# Particle-Gateway.net
KiCad netlist of a schematic drawn in EAGLE
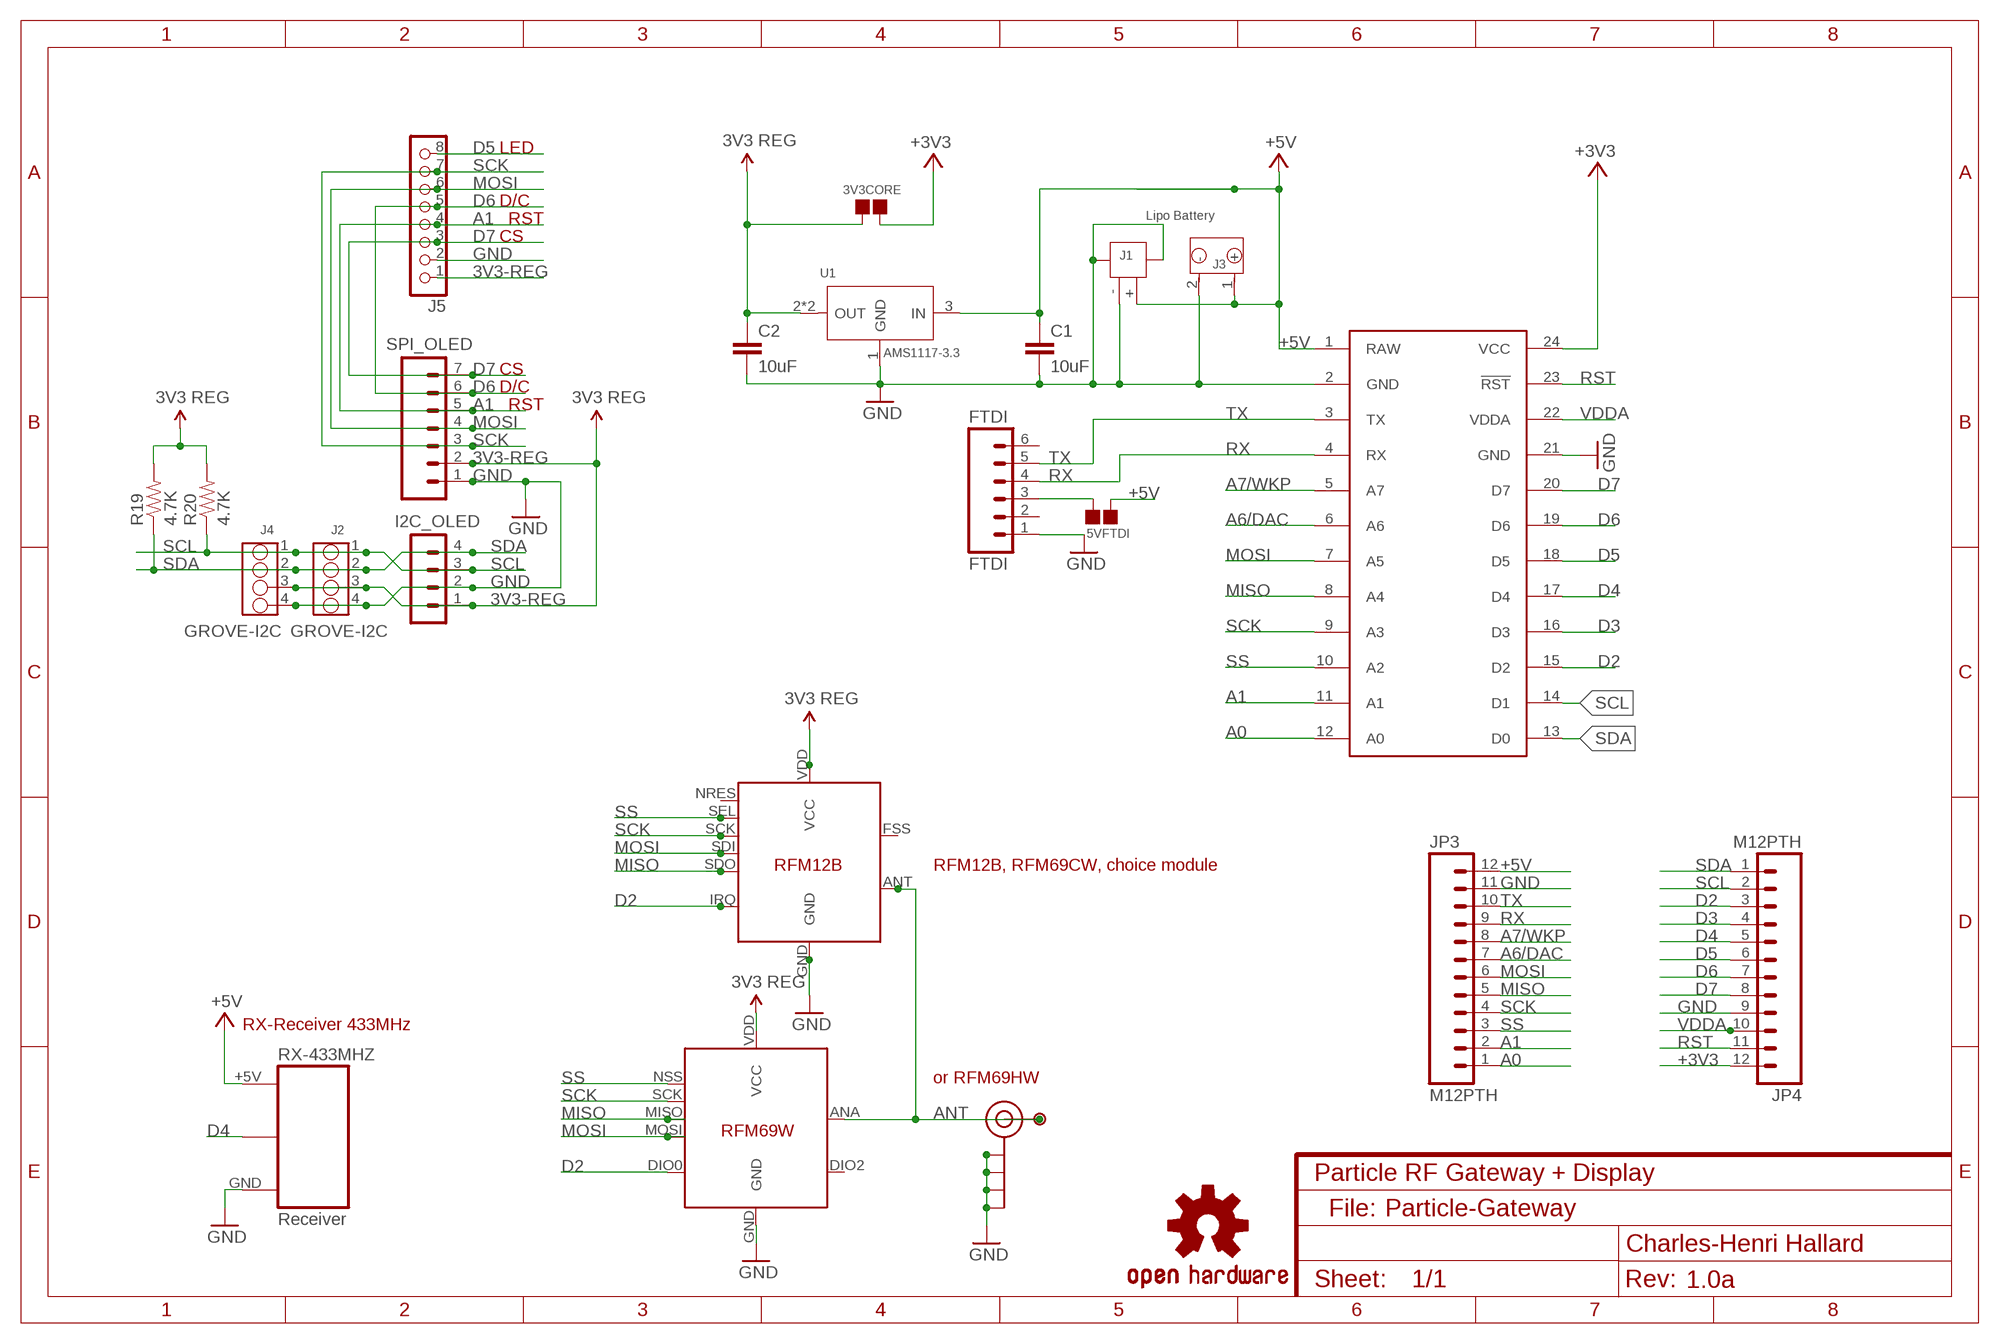
[diagram p0: schematic, sheet 1]

(export (version "E")
  (design (tool "Eeschema 10.0.6"))
  (components
    (comp (ref "3V3CORE")
      (value "PAD-JUMPER-2P")
      (footprint "eagle-import:2P-SMD-1.78X1.27")
      (fields (field (name "PARTNO") "DNP"))
      (libsource (lib "eagle-import") (part "PAD-JUMPER-2P"))
    )
    (comp (ref "5VFTDI")
      (value "PAD-JUMPER-2P")
      (footprint "eagle-import:2P-SMD-1.78X1.27")
      (fields (field (name "PARTNO") "DNP"))
      (libsource (lib "eagle-import") (part "PAD-JUMPER-2P"))
    )
    (comp (ref "C1")
      (value "10uF")
      (footprint "eagle-import:0805-CAP")
      (libsource (lib "eagle-import") (part "CAP0805-CAP"))
    )
    (comp (ref "C2")
      (value "10uF")
      (footprint "eagle-import:0805-CAP")
      (libsource (lib "eagle-import") (part "CAP0805-CAP"))
    )
    (comp (ref "FTDI")
      (value "FTDI")
      (footprint "eagle-import:1X06")
      (libsource (lib "eagle-import") (part "M06SIP"))
    )
    (comp (ref "I2C_OLED")
      (value "CON_HEADER_1X04'SMALL''")
      (footprint "eagle-import:M1X4")
      (libsource (lib "eagle-import") (part "CON_HEADER_1X04'SMALL''"))
    )
    (comp (ref "J$1")
      (value "SMA_EDGE")
      (footprint "eagle-import:SMA-EDGE")
      (libsource (lib "eagle-import") (part "SMA_EDGE"))
    )
    (comp (ref "J1")
      (value "JST-2P-SMD'2.0'")
      (footprint "eagle-import:2P-SMD-2.0-90D")
      (libsource (lib "eagle-import") (part "JST-2P-SMD'2.0'"))
    )
    (comp (ref "J2")
      (value "GROVE-I2C")
      (footprint "eagle-import:4P-2.0-90D")
      (libsource (lib "eagle-import") (part "GROVE-4P-2.0-3470140P1"))
    )
    (comp (ref "J3")
      (value "Lipo Battery")
      (footprint "eagle-import:2P-2.0-90D")
      (libsource (lib "eagle-import") (part "JST-2P-PW-3410070P1"))
    )
    (comp (ref "J4")
      (value "GROVE-I2C")
      (footprint "eagle-import:4P-2.0")
      (libsource (lib "eagle-import") (part "GROVE-4P-2.0-3470130P1"))
    )
    (comp (ref "J5")
      (value "CON_HEADER_1X08-PTH")
      (footprint "eagle-import:M1X8")
      (libsource (lib "eagle-import") (part "CON_HEADER_1X08-PTH"))
    )
    (comp (ref "JP3")
      (value "M12PTH")
      (footprint "eagle-import:1X12-SMALL-PADS")
      (libsource (lib "eagle-import") (part "M12PTH"))
    )
    (comp (ref "JP4")
      (value "M12PTH")
      (footprint "eagle-import:1X12-SMALL-PADS")
      (libsource (lib "eagle-import") (part "M12PTH"))
    )
    (comp (ref "LOGO2")
      (value "OSHW-LOGOL")
      (footprint "eagle-import:OSHW-LOGO-L")
      (libsource (lib "eagle-import") (part "OSHW-LOGOL"))
    )
    (comp (ref "P1")
      (value "PADSMALL")
      (footprint "eagle-import:PAD-SMALL")
      (libsource (lib "eagle-import") (part "PADSMALL"))
    )
    (comp (ref "R19")
      (value "4.7K")
      (footprint "eagle-import:0805-RES")
      (libsource (lib "eagle-import") (part "RESISTOR0805-RES"))
    )
    (comp (ref "R20")
      (value "4.7K")
      (footprint "eagle-import:0805-RES")
      (libsource (lib "eagle-import") (part "RESISTOR0805-RES"))
    )
    (comp (ref "RX-433MHZ")
      (value "Receiver")
      (footprint "eagle-import:RF-LINK_RX_NO_SILK")
      (libsource (lib "eagle-import") (part "RF-LINK_RX"))
    )
    (comp (ref "SPARKCORE")
      (value "SPARK_CORECORE")
      (footprint "eagle-import:SPARK_CORE")
      (libsource (lib "eagle-import") (part "SPARK_CORECORE"))
    )
    (comp (ref "SPI_OLED")
      (value "CON_HEADER_1X07'SMALL'")
      (footprint "eagle-import:M1X7")
      (libsource (lib "eagle-import") (part "CON_HEADER_1X07'SMALL'"))
    )
    (comp (ref "U$2")
      (value "RFM12B")
      (footprint "eagle-import:RFM12B-MINPADS")
      (libsource (lib "eagle-import") (part "RFM12B"))
    )
    (comp (ref "U$3")
      (value "RFM69W")
      (footprint "eagle-import:RFM69W-MINPADS")
      (libsource (lib "eagle-import") (part "RFM69W"))
    )
    (comp (ref "U-FL")
      (value "U.FL")
      (footprint "eagle-import:U.FL")
      (libsource (lib "eagle-import") (part "U.FL"))
    )
    (comp (ref "U1")
      (value "AMS1117-3.3")
      (footprint "eagle-import:SOT223")
      (libsource (lib "eagle-import") (part "CJ1117-3.3-1310190P1"))
    )
  )
  (nets
    (net (code "1") (name "+3V3") (class "Default")
      (node (ref "3V3CORE") (pin "2") (pinfunction "2_2") (pintype "bidirectional"))
      (node (ref "JP4") (pin "12") (pinfunction "12_12") (pintype "passive"))
      (node (ref "SPARKCORE") (pin "24") (pinfunction "VCC_24") (pintype "power_in"))
    )
    (net (code "2") (name "+5V") (class "Default")
      (node (ref "5VFTDI") (pin "1") (pinfunction "1_1") (pintype "bidirectional"))
      (node (ref "C1") (pin "1") (pinfunction "1_1") (pintype "passive"))
      (node (ref "J1") (pin "+") (pinfunction "1_+") (pintype "bidirectional"))
      (node (ref "J3") (pin "1") (pinfunction "+_1") (pintype "bidirectional"))
      (node (ref "JP3") (pin "12") (pinfunction "12_12") (pintype "passive"))
      (node (ref "RX-433MHZ") (pin "+5V") (pinfunction "+5V_+5V") (pintype "power_in"))
      (node (ref "SPARKCORE") (pin "1") (pinfunction "RAW_1") (pintype "power_in"))
      (node (ref "U1") (pin "3") (pinfunction "IN_3") (pintype "bidirectional"))
    )
    (net (code "3") (name "/A0") (class "Default")
      (node (ref "JP3") (pin "1") (pinfunction "1_1") (pintype "passive"))
      (node (ref "SPARKCORE") (pin "12") (pinfunction "A0_12") (pintype "bidirectional"))
    )
    (net (code "4") (name "/A1") (class "Default")
      (node (ref "J5") (pin "4") (pinfunction "4_4") (pintype "passive"))
      (node (ref "JP3") (pin "2") (pinfunction "2_2") (pintype "passive"))
      (node (ref "SPARKCORE") (pin "11") (pinfunction "A1_11") (pintype "bidirectional"))
      (node (ref "SPI_OLED") (pin "5") (pinfunction "5_5") (pintype "passive"))
    )
    (net (code "5") (name "/A6{slash}DAC") (class "Default")
      (node (ref "JP3") (pin "7") (pinfunction "7_7") (pintype "passive"))
      (node (ref "SPARKCORE") (pin "6") (pinfunction "A6_6") (pintype "bidirectional"))
    )
    (net (code "6") (name "/A7{slash}WKP") (class "Default")
      (node (ref "JP3") (pin "8") (pinfunction "8_8") (pintype "passive"))
      (node (ref "SPARKCORE") (pin "5") (pinfunction "A7_5") (pintype "bidirectional"))
    )
    (net (code "7") (name "/ANT") (class "Default")
      (node (ref "J$1") (pin "SIG") (pinfunction "SIGNAL_SIG") (pintype "bidirectional"))
      (node (ref "P1") (pin "1") (pinfunction "1_1") (pintype "bidirectional"))
      (node (ref "U$2") (pin "ANT") (pinfunction "ANT_ANT") (pintype "passive"))
      (node (ref "U$3") (pin "ANA") (pinfunction "ANT_ANA") (pintype "passive"))
      (node (ref "U-FL") (pin "3") (pinfunction "SIGNAL_3") (pintype "passive"))
    )
    (net (code "8") (name "/D2") (class "Default")
      (node (ref "JP4") (pin "3") (pinfunction "3_3") (pintype "passive"))
      (node (ref "SPARKCORE") (pin "15") (pinfunction "D2_15") (pintype "bidirectional"))
      (node (ref "U$2") (pin "IRQ") (pinfunction "IRQ_IRQ") (pintype "open_collector"))
      (node (ref "U$3") (pin "DIO0") (pinfunction "DIO0_DIO0") (pintype "open_collector"))
    )
    (net (code "9") (name "/D3") (class "Default")
      (node (ref "JP4") (pin "4") (pinfunction "4_4") (pintype "passive"))
      (node (ref "SPARKCORE") (pin "16") (pinfunction "D3_16") (pintype "bidirectional"))
    )
    (net (code "10") (name "/D4") (class "Default")
      (node (ref "JP4") (pin "5") (pinfunction "5_5") (pintype "passive"))
      (node (ref "RX-433MHZ") (pin "DATA@1") (pinfunction "DATA_DATA@1") (pintype "output"))
      (node (ref "RX-433MHZ") (pin "DATA@2") (pinfunction "DATA_DATA@2") (pintype "output"))
      (node (ref "SPARKCORE") (pin "17") (pinfunction "D4_17") (pintype "bidirectional"))
    )
    (net (code "11") (name "/D5") (class "Default")
      (node (ref "J5") (pin "8") (pinfunction "8_8") (pintype "passive"))
      (node (ref "JP4") (pin "6") (pinfunction "6_6") (pintype "passive"))
      (node (ref "SPARKCORE") (pin "18") (pinfunction "D5_18") (pintype "bidirectional"))
    )
    (net (code "12") (name "/D6") (class "Default")
      (node (ref "J5") (pin "5") (pinfunction "5_5") (pintype "passive"))
      (node (ref "JP4") (pin "7") (pinfunction "7_7") (pintype "passive"))
      (node (ref "SPARKCORE") (pin "19") (pinfunction "D6_19") (pintype "bidirectional"))
      (node (ref "SPI_OLED") (pin "6") (pinfunction "6_6") (pintype "passive"))
    )
    (net (code "13") (name "/D7") (class "Default")
      (node (ref "J5") (pin "3") (pinfunction "3_3") (pintype "passive"))
      (node (ref "JP4") (pin "8") (pinfunction "8_8") (pintype "passive"))
      (node (ref "SPARKCORE") (pin "20") (pinfunction "D7_20") (pintype "bidirectional"))
      (node (ref "SPI_OLED") (pin "7") (pinfunction "7_7") (pintype "passive"))
    )
    (net (code "14") (name "/MISO") (class "Default")
      (node (ref "JP3") (pin "5") (pinfunction "5_5") (pintype "passive"))
      (node (ref "SPARKCORE") (pin "8") (pinfunction "A4_8") (pintype "bidirectional"))
      (node (ref "U$2") (pin "SDO") (pinfunction "SDO_SDO") (pintype "output"))
      (node (ref "U$3") (pin "MISO") (pinfunction "MISO_MISO") (pintype "input"))
    )
    (net (code "15") (name "/MOSI") (class "Default")
      (node (ref "J5") (pin "6") (pinfunction "6_6") (pintype "passive"))
      (node (ref "JP3") (pin "6") (pinfunction "6_6") (pintype "passive"))
      (node (ref "SPARKCORE") (pin "7") (pinfunction "A5_7") (pintype "bidirectional"))
      (node (ref "SPI_OLED") (pin "4") (pinfunction "4_4") (pintype "passive"))
      (node (ref "U$2") (pin "SDI") (pinfunction "SDI_SDI") (pintype "input"))
      (node (ref "U$3") (pin "MOSI") (pinfunction "MOSI_MOSI") (pintype "output"))
    )
    (net (code "16") (name "/RST") (class "Default")
      (node (ref "JP4") (pin "11") (pinfunction "11_11") (pintype "passive"))
      (node (ref "SPARKCORE") (pin "23") (pinfunction "~{RST}_23") (pintype "bidirectional"))
    )
    (net (code "17") (name "/RX") (class "Default")
      (node (ref "FTDI") (pin "4") (pinfunction "4_4") (pintype "passive"))
      (node (ref "JP3") (pin "9") (pinfunction "9_9") (pintype "passive"))
      (node (ref "SPARKCORE") (pin "4") (pinfunction "RX_4") (pintype "bidirectional"))
    )
    (net (code "18") (name "/SCK") (class "Default")
      (node (ref "J5") (pin "7") (pinfunction "7_7") (pintype "passive"))
      (node (ref "JP3") (pin "4") (pinfunction "4_4") (pintype "passive"))
      (node (ref "SPARKCORE") (pin "9") (pinfunction "A3_9") (pintype "bidirectional"))
      (node (ref "SPI_OLED") (pin "3") (pinfunction "3_3") (pintype "passive"))
      (node (ref "U$2") (pin "SCK") (pinfunction "SCK_SCK") (pintype "input"))
      (node (ref "U$3") (pin "SCK") (pinfunction "SCK_SCK") (pintype "input"))
    )
    (net (code "19") (name "/SS") (class "Default")
      (node (ref "JP3") (pin "3") (pinfunction "3_3") (pintype "passive"))
      (node (ref "SPARKCORE") (pin "10") (pinfunction "A2_10") (pintype "bidirectional"))
      (node (ref "U$2") (pin "SEL") (pinfunction "SEL_SEL") (pintype "input"))
      (node (ref "U$3") (pin "NSS") (pinfunction "SEL_NSS") (pintype "input"))
    )
    (net (code "20") (name "/TX") (class "Default")
      (node (ref "FTDI") (pin "5") (pinfunction "5_5") (pintype "passive"))
      (node (ref "JP3") (pin "10") (pinfunction "10_10") (pintype "passive"))
      (node (ref "SPARKCORE") (pin "3") (pinfunction "TX_3") (pintype "bidirectional"))
    )
    (net (code "21") (name "/VDDA") (class "Default")
      (node (ref "JP4") (pin "10") (pinfunction "10_10") (pintype "passive"))
      (node (ref "SPARKCORE") (pin "22") (pinfunction "VDDA_22") (pintype "power_in"))
    )
    (net (code "22") (name "3V3 REG") (class "Default")
      (node (ref "3V3CORE") (pin "1") (pinfunction "1_1") (pintype "bidirectional"))
      (node (ref "C2") (pin "1") (pinfunction "1_1") (pintype "passive"))
      (node (ref "I2C_OLED") (pin "1") (pinfunction "1_1") (pintype "passive"))
      (node (ref "J2") (pin "3") (pinfunction "3_3") (pintype "bidirectional"))
      (node (ref "J4") (pin "3") (pinfunction "3_3") (pintype "bidirectional"))
      (node (ref "J5") (pin "1") (pinfunction "1_1") (pintype "passive"))
      (node (ref "R19") (pin "2") (pinfunction "2_2") (pintype "passive"))
      (node (ref "R20") (pin "2") (pinfunction "2_2") (pintype "passive"))
      (node (ref "SPI_OLED") (pin "2") (pinfunction "2_2") (pintype "passive"))
      (node (ref "U$2") (pin "VDD") (pinfunction "VCC_VDD") (pintype "power_in"))
      (node (ref "U$3") (pin "VDD") (pinfunction "VCC_VDD") (pintype "power_in"))
      (node (ref "U1") (pin "2") (pinfunction "OUT_2") (pintype "bidirectional"))
      (node (ref "U1") (pin "TER") (pinfunction "OUT_TER") (pintype "bidirectional"))
    )
    (net (code "23") (name "GND") (class "Default")
      (node (ref "C1") (pin "2") (pinfunction "2_2") (pintype "passive"))
      (node (ref "C2") (pin "2") (pinfunction "2_2") (pintype "passive"))
      (node (ref "FTDI") (pin "1") (pinfunction "1_1") (pintype "passive"))
      (node (ref "I2C_OLED") (pin "2") (pinfunction "2_2") (pintype "passive"))
      (node (ref "J$1") (pin "GND@0") (pinfunction "GND_GND@0") (pintype "bidirectional"))
      (node (ref "J$1") (pin "GND@1") (pinfunction "GND_GND@1") (pintype "bidirectional"))
      (node (ref "J$1") (pin "GND@2") (pinfunction "GND_GND@2") (pintype "bidirectional"))
      (node (ref "J$1") (pin "GND@3") (pinfunction "GND_GND@3") (pintype "bidirectional"))
      (node (ref "J1") (pin "-") (pinfunction "2_-") (pintype "bidirectional"))
      (node (ref "J1") (pin "3") (pinfunction "3_3") (pintype "bidirectional"))
      (node (ref "J1") (pin "4") (pinfunction "4_4") (pintype "bidirectional"))
      (node (ref "J2") (pin "4") (pinfunction "4_4") (pintype "bidirectional"))
      (node (ref "J3") (pin "2") (pinfunction "-_2") (pintype "bidirectional"))
      (node (ref "J4") (pin "4") (pinfunction "4_4") (pintype "bidirectional"))
      (node (ref "J5") (pin "2") (pinfunction "2_2") (pintype "passive"))
      (node (ref "JP3") (pin "11") (pinfunction "11_11") (pintype "passive"))
      (node (ref "JP4") (pin "9") (pinfunction "9_9") (pintype "passive"))
      (node (ref "RX-433MHZ") (pin "GND") (pinfunction "GND_GND") (pintype "power_in"))
      (node (ref "SPARKCORE") (pin "2") (pinfunction "GND_2") (pintype "power_in"))
      (node (ref "SPARKCORE") (pin "21") (pinfunction "GND_21") (pintype "power_in"))
      (node (ref "SPI_OLED") (pin "1") (pinfunction "1_1") (pintype "passive"))
      (node (ref "U$2") (pin "GND") (pinfunction "GND_GND") (pintype "power_in"))
      (node (ref "U$3") (pin "GND") (pinfunction "GND_GND") (pintype "power_in"))
      (node (ref "U-FL") (pin "1") (pinfunction "GND_1") (pintype "passive"))
      (node (ref "U-FL") (pin "2") (pinfunction "GND_2") (pintype "passive"))
      (node (ref "U1") (pin "1") (pinfunction "GND_1") (pintype "bidirectional"))
    )
    (net (code "24") (name "Net-(5VFTDI-Pad2)") (class "Default")
      (node (ref "5VFTDI") (pin "2") (pinfunction "2_2") (pintype "bidirectional"))
      (node (ref "FTDI") (pin "3") (pinfunction "3_3") (pintype "passive"))
    )
    (net (code "25") (name "SCL") (class "Default")
      (node (ref "I2C_OLED") (pin "3") (pinfunction "3_3") (pintype "passive"))
      (node (ref "J2") (pin "1") (pinfunction "1_1") (pintype "bidirectional"))
      (node (ref "J4") (pin "1") (pinfunction "1_1") (pintype "bidirectional"))
      (node (ref "JP4") (pin "2") (pinfunction "2_2") (pintype "passive"))
      (node (ref "R20") (pin "1") (pinfunction "1_1") (pintype "passive"))
      (node (ref "SPARKCORE") (pin "14") (pinfunction "D1_14") (pintype "bidirectional"))
    )
    (net (code "26") (name "SDA") (class "Default")
      (node (ref "I2C_OLED") (pin "4") (pinfunction "4_4") (pintype "passive"))
      (node (ref "J2") (pin "2") (pinfunction "2_2") (pintype "bidirectional"))
      (node (ref "J4") (pin "2") (pinfunction "2_2") (pintype "bidirectional"))
      (node (ref "JP4") (pin "1") (pinfunction "1_1") (pintype "passive"))
      (node (ref "R19") (pin "1") (pinfunction "1_1") (pintype "passive"))
      (node (ref "SPARKCORE") (pin "13") (pinfunction "D0_13") (pintype "bidirectional"))
    )
    (net (code "27") (name "unconnected-(FTDI-Pad2)") (class "Default")
      (node (ref "FTDI") (pin "2") (pinfunction "2_2") (pintype "passive"))
    )
    (net (code "28") (name "unconnected-(FTDI-Pad6)") (class "Default")
      (node (ref "FTDI") (pin "6") (pinfunction "6_6") (pintype "passive"))
    )
    (net (code "29") (name "unconnected-(U$2-FFS-PadFSS)") (class "Default")
      (node (ref "U$2") (pin "FSS") (pinfunction "FFS_FSS") (pintype "bidirectional"))
    )
    (net (code "30") (name "unconnected-(U$2-PadNRES)") (class "Default")
      (node (ref "U$2") (pin "NRES") (pinfunction "NRES_NRES") (pintype "input"))
    )
    (net (code "31") (name "unconnected-(U$3-PadDIO2)") (class "Default")
      (node (ref "U$3") (pin "DIO2") (pinfunction "DIO2_DIO2") (pintype "open_collector"))
    )
  )
)
